# dev_kit.net
KiCad netlist of a schematic drawn in EasyEDA
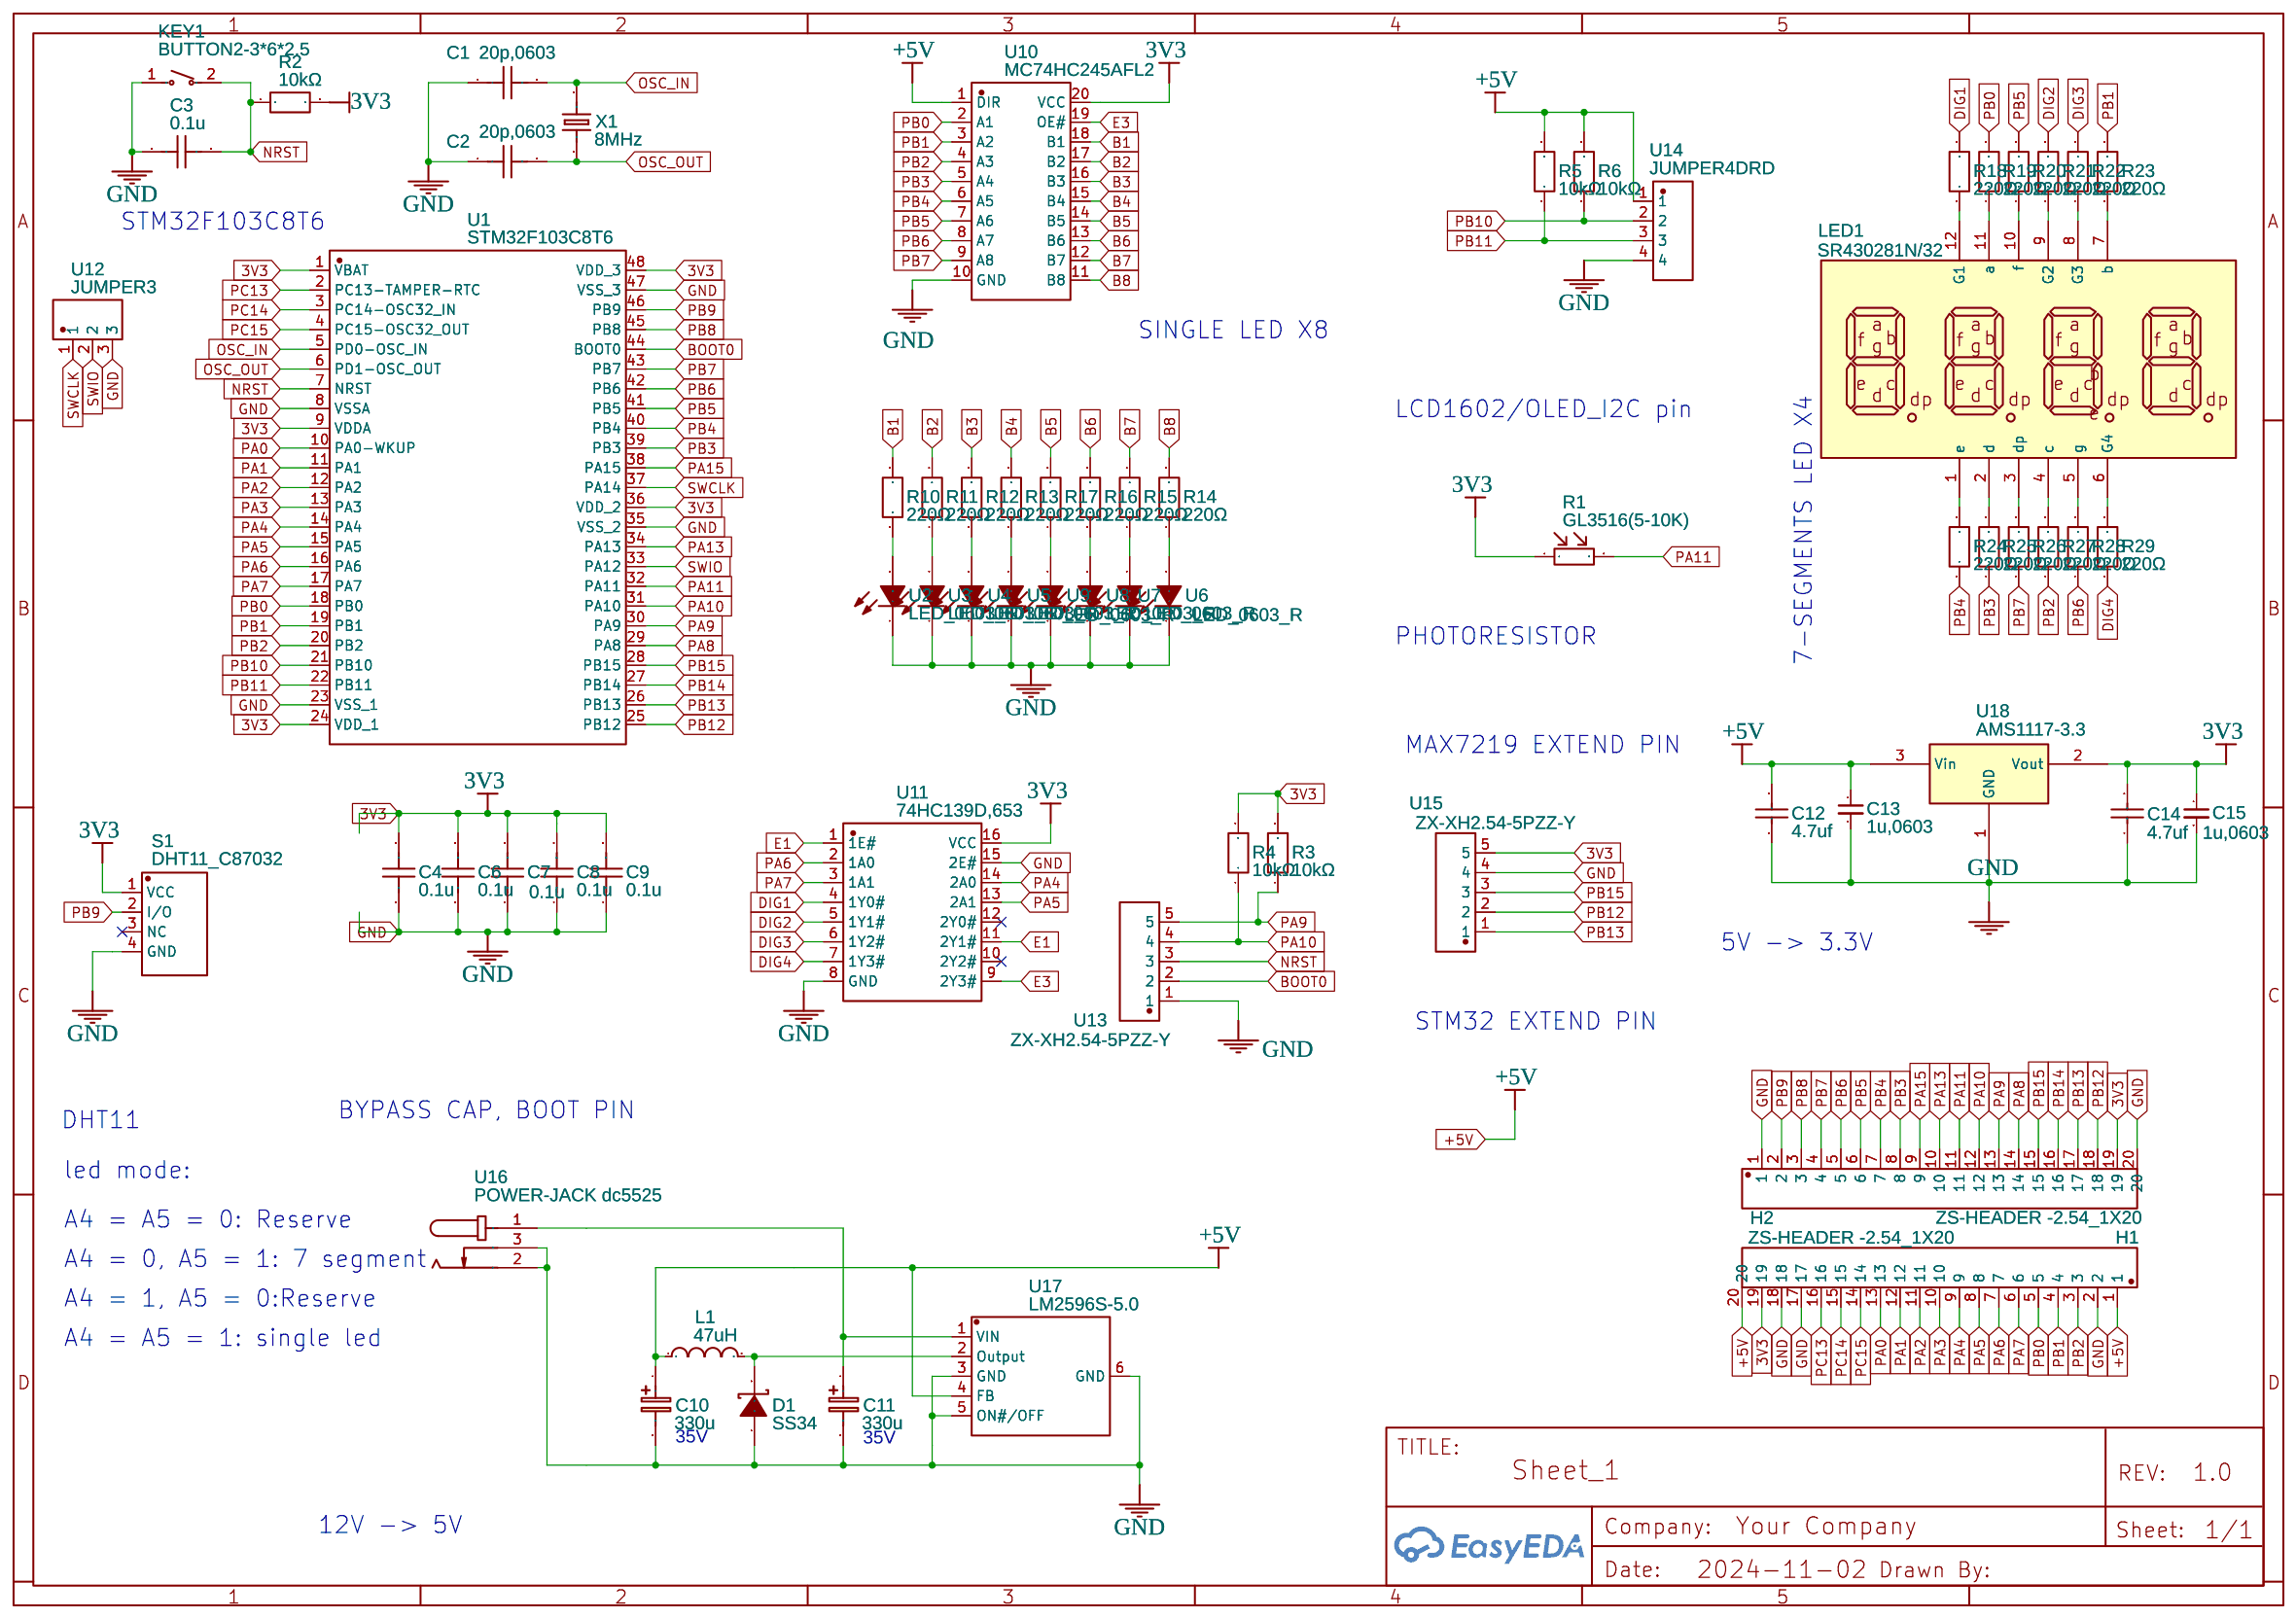
[diagram p0: schematic sheet]

(export (version "E")
  (design (tool "Eeschema 10.0.6"))
  (components
    (comp (ref "C1") (value "20p,0603") (libsource (lib "") (part "C_0603_US_1")))
    (comp (ref "C2") (value "20p,0603") (libsource (lib "") (part "C_0603_US_1")))
    (comp (ref "C3") (value "0.1u") (libsource (lib "") (part "C_0603_US_1")))
    (comp (ref "C4") (value "0.1u") (libsource (lib "") (part "C_0603_US")))
    (comp (ref "C6") (value "0.1u") (libsource (lib "") (part "C_0603_US")))
    (comp (ref "C7") (value "0.1u") (libsource (lib "") (part "C_0603_US")))
    (comp (ref "C8") (value "0.1u") (libsource (lib "") (part "C_0603_US")))
    (comp (ref "C9") (value "0.1u") (libsource (lib "") (part "C_0603_US")))
    (comp (ref "C10")
      (value "330u")
      (fields (field (name "Manufacturer Part") "?"))
      (libsource (lib "") (part "Cap_Electrolytic(SMD)_D8.0XH10.5_EU"))
    )
    (comp (ref "C11")
      (value "330u")
      (fields (field (name "Manufacturer Part") "?"))
      (libsource (lib "") (part "Cap_Electrolytic(SMD)_D8.0XH10.5_EU"))
    )
    (comp (ref "C12")
      (value "4.7uf")
      (fields (field (name "Manufacturer Part") "?"))
      (libsource (lib "") (part "Unknown_890_-400"))
    )
    (comp (ref "C13") (value "1u,0603") (libsource (lib "") (part "C_0603")))
    (comp (ref "C14")
      (value "4.7uf")
      (fields (field (name "Manufacturer Part") "?"))
      (libsource (lib "") (part "Unknown_1070_-400"))
    )
    (comp (ref "C15") (value "1u,0603") (libsource (lib "") (part "C_0603")))
    (comp (ref "D1")
      (value "SS34")
      (fields (field (name "Manufacturer") "Yenji"))
      (libsource (lib "") (part "Unknown_375_-105"))
    )
    (comp (ref "H1") (value "ZS-HEADER -2.54_1X20") (libsource (lib "") (part "ZS-HEADER -2.54_1X20")))
    (comp (ref "H2") (value "ZS-HEADER -2.54_1X20") (libsource (lib "") (part "ZS-HEADER -2.54_1X20_1")))
    (comp (ref "KEY1") (value "BUTTON2-3*6*2.5") (libsource (lib "") (part "BUTTON2-3*6*2.5")))
    (comp (ref "L1")
      (value "47uH")
      (fields (field (name "Manufacturer Part") "CDRH127NP-470MC") (field (name "Manufacturer") "Sumida"))
      (libsource (lib "") (part "CDRH127NP-470MC"))
    )
    (comp (ref "LED1")
      (value "SR430281N/32")
      (fields (field (name "Manufacturer") "ARKLED(方舟)"))
      (libsource (lib "") (part "SR430281N/32"))
    )
    (comp (ref "R1")
      (value "GL3516(5-10K)")
      (fields (field (name "Manufacturer Part") "GL3516（5-10K）") (field (name "Manufacturer") "JCHL(晶创和立)"))
      (libsource (lib "") (part "GL3516(5-10K)"))
    )
    (comp (ref "R2")
      (value "10kΩ")
      (fields (field (name "Manufacturer Part") "TD03E1002BT") (field (name "Manufacturer") "FH(风华)"))
      (libsource (lib "") (part "TD03E1002BT_1"))
    )
    (comp (ref "R3")
      (value "10kΩ")
      (fields (field (name "Manufacturer Part") "TD03E1002BT") (field (name "Manufacturer") "FH(风华)"))
      (libsource (lib "") (part "TD03E1002BT"))
    )
    (comp (ref "R4")
      (value "10kΩ")
      (fields (field (name "Manufacturer Part") "TD03E1002BT") (field (name "Manufacturer") "FH(风华)"))
      (libsource (lib "") (part "TD03E1002BT"))
    )
    (comp (ref "R5")
      (value "10kΩ")
      (fields (field (name "Manufacturer Part") "TD03E1002BT") (field (name "Manufacturer") "FH(风华)"))
      (libsource (lib "") (part "TD03E1002BT"))
    )
    (comp (ref "R6")
      (value "10kΩ")
      (fields (field (name "Manufacturer Part") "TD03E1002BT") (field (name "Manufacturer") "FH(风华)"))
      (libsource (lib "") (part "TD03E1002BT"))
    )
    (comp (ref "R10")
      (value "220Ω")
      (fields
        (field (name "Manufacturer Part") "CRCW0603220RFKEA")
        (field (name "Manufacturer") "VISHAY(威世)")
      )
      (libsource (lib "") (part "CRCW0603220RFKEA"))
    )
    (comp (ref "R11")
      (value "220Ω")
      (fields
        (field (name "Manufacturer Part") "CRCW0603220RFKEA")
        (field (name "Manufacturer") "VISHAY(威世)")
      )
      (libsource (lib "") (part "CRCW0603220RFKEA"))
    )
    (comp (ref "R12")
      (value "220Ω")
      (fields
        (field (name "Manufacturer Part") "CRCW0603220RFKEA")
        (field (name "Manufacturer") "VISHAY(威世)")
      )
      (libsource (lib "") (part "CRCW0603220RFKEA"))
    )
    (comp (ref "R13")
      (value "220Ω")
      (fields
        (field (name "Manufacturer Part") "CRCW0603220RFKEA")
        (field (name "Manufacturer") "VISHAY(威世)")
      )
      (libsource (lib "") (part "CRCW0603220RFKEA"))
    )
    (comp (ref "R14")
      (value "220Ω")
      (fields
        (field (name "Manufacturer Part") "CRCW0603220RFKEA")
        (field (name "Manufacturer") "VISHAY(威世)")
      )
      (libsource (lib "") (part "CRCW0603220RFKEA"))
    )
    (comp (ref "R15")
      (value "220Ω")
      (fields
        (field (name "Manufacturer Part") "CRCW0603220RFKEA")
        (field (name "Manufacturer") "VISHAY(威世)")
      )
      (libsource (lib "") (part "CRCW0603220RFKEA"))
    )
    (comp (ref "R16")
      (value "220Ω")
      (fields
        (field (name "Manufacturer Part") "CRCW0603220RFKEA")
        (field (name "Manufacturer") "VISHAY(威世)")
      )
      (libsource (lib "") (part "CRCW0603220RFKEA"))
    )
    (comp (ref "R17")
      (value "220Ω")
      (fields
        (field (name "Manufacturer Part") "CRCW0603220RFKEA")
        (field (name "Manufacturer") "VISHAY(威世)")
      )
      (libsource (lib "") (part "CRCW0603220RFKEA"))
    )
    (comp (ref "R18")
      (value "220Ω")
      (fields
        (field (name "Manufacturer Part") "CRCW0603220RFKEA")
        (field (name "Manufacturer") "VISHAY(威世)")
      )
      (libsource (lib "") (part "CRCW0603220RFKEA"))
    )
    (comp (ref "R19")
      (value "220Ω")
      (fields
        (field (name "Manufacturer Part") "CRCW0603220RFKEA")
        (field (name "Manufacturer") "VISHAY(威世)")
      )
      (libsource (lib "") (part "CRCW0603220RFKEA"))
    )
    (comp (ref "R20")
      (value "220Ω")
      (fields
        (field (name "Manufacturer Part") "CRCW0603220RFKEA")
        (field (name "Manufacturer") "VISHAY(威世)")
      )
      (libsource (lib "") (part "CRCW0603220RFKEA"))
    )
    (comp (ref "R21")
      (value "220Ω")
      (fields
        (field (name "Manufacturer Part") "CRCW0603220RFKEA")
        (field (name "Manufacturer") "VISHAY(威世)")
      )
      (libsource (lib "") (part "CRCW0603220RFKEA"))
    )
    (comp (ref "R22")
      (value "220Ω")
      (fields
        (field (name "Manufacturer Part") "CRCW0603220RFKEA")
        (field (name "Manufacturer") "VISHAY(威世)")
      )
      (libsource (lib "") (part "CRCW0603220RFKEA"))
    )
    (comp (ref "R23")
      (value "220Ω")
      (fields
        (field (name "Manufacturer Part") "CRCW0603220RFKEA")
        (field (name "Manufacturer") "VISHAY(威世)")
      )
      (libsource (lib "") (part "CRCW0603220RFKEA"))
    )
    (comp (ref "R24")
      (value "220Ω")
      (fields
        (field (name "Manufacturer Part") "CRCW0603220RFKEA")
        (field (name "Manufacturer") "VISHAY(威世)")
      )
      (libsource (lib "") (part "CRCW0603220RFKEA"))
    )
    (comp (ref "R25")
      (value "220Ω")
      (fields
        (field (name "Manufacturer Part") "CRCW0603220RFKEA")
        (field (name "Manufacturer") "VISHAY(威世)")
      )
      (libsource (lib "") (part "CRCW0603220RFKEA"))
    )
    (comp (ref "R26")
      (value "220Ω")
      (fields
        (field (name "Manufacturer Part") "CRCW0603220RFKEA")
        (field (name "Manufacturer") "VISHAY(威世)")
      )
      (libsource (lib "") (part "CRCW0603220RFKEA"))
    )
    (comp (ref "R27")
      (value "220Ω")
      (fields
        (field (name "Manufacturer Part") "CRCW0603220RFKEA")
        (field (name "Manufacturer") "VISHAY(威世)")
      )
      (libsource (lib "") (part "CRCW0603220RFKEA"))
    )
    (comp (ref "R28")
      (value "220Ω")
      (fields
        (field (name "Manufacturer Part") "CRCW0603220RFKEA")
        (field (name "Manufacturer") "VISHAY(威世)")
      )
      (libsource (lib "") (part "CRCW0603220RFKEA"))
    )
    (comp (ref "R29")
      (value "220Ω")
      (fields
        (field (name "Manufacturer Part") "CRCW0603220RFKEA")
        (field (name "Manufacturer") "VISHAY(威世)")
      )
      (libsource (lib "") (part "CRCW0603220RFKEA"))
    )
    (comp (ref "S1")
      (value "DHT11_C87032")
      (fields (field (name "Manufacturer Part") "DHT11") (field (name "Manufacturer") "AOSONG"))
      (libsource (lib "") (part "DHT11_C87032"))
    )
    (comp (ref "U1")
      (value "STM32F103C8T6")
      (fields (field (name "Manufacturer") "ST(意法半导体)"))
      (libsource (lib "") (part "STM32F103C8T6"))
    )
    (comp (ref "U2") (value "LED_0603_R") (libsource (lib "") (part "LED_0603_R")))
    (comp (ref "U3") (value "LED_0603_R") (libsource (lib "") (part "LED_0603_R")))
    (comp (ref "U4") (value "LED_0603_R") (libsource (lib "") (part "LED_0603_R")))
    (comp (ref "U5") (value "LED_0603_R") (libsource (lib "") (part "LED_0603_R")))
    (comp (ref "U6") (value "LED_0603_R") (libsource (lib "") (part "LED_0603_R")))
    (comp (ref "U7") (value "LED_0603_R") (libsource (lib "") (part "LED_0603_R")))
    (comp (ref "U8") (value "LED_0603_R") (libsource (lib "") (part "LED_0603_R")))
    (comp (ref "U9") (value "LED_0603_R") (libsource (lib "") (part "LED_0603_R")))
    (comp (ref "U10")
      (value "MC74HC245AFL2")
      (fields (field (name "Manufacturer") "MOTOROLA(摩托罗拉)"))
      (libsource (lib "") (part "MC74HC245AFL2"))
    )
    (comp (ref "U11")
      (value "74HC139D,653")
      (fields (field (name "Manufacturer") "Nexperia(安世)"))
      (libsource (lib "") (part "74HC139D,653"))
    )
    (comp (ref "U12")
      (value "JUMPER3")
      (fields (field (name "Manufacturer Part") "Jumper3"))
      (libsource (lib "") (part "JUMPER3"))
    )
    (comp (ref "U13")
      (value "ZX-XH2.54-5PZZ-Y")
      (fields (field (name "Manufacturer") "Megastar(兆星)"))
      (libsource (lib "") (part "ZX-XH2.54-5PZZ-Y"))
    )
    (comp (ref "U14")
      (value "JUMPER4DRD")
      (fields (field (name "Manufacturer Part") "Jumper4"))
      (libsource (lib "") (part "JUMPER4DRD"))
    )
    (comp (ref "U15")
      (value "ZX-XH2.54-5PZZ-Y")
      (fields (field (name "Manufacturer") "Megastar(兆星)"))
      (libsource (lib "") (part "ZX-XH2.54-5PZZ-Y"))
    )
    (comp (ref "U16")
      (value "POWER-JACK dc5525")
      (fields (field (name "Manufacturer Part") "POWER-JACK"))
      (libsource (lib "") (part "POWER-JACK dc5525"))
    )
    (comp (ref "U17")
      (value "LM2596S-5.0")
      (fields
        (field (name "Manufacturer Part") "LM2596S-5.0/NOPB")
        (field (name "Manufacturer") "Texas Instruments")
      )
      (libsource (lib "") (part "Unknown_520_-120"))
    )
    (comp (ref "U18")
      (value "AMS1117-3.3")
      (fields (field (name "Manufacturer Part") "?"))
      (libsource (lib "") (part "Unknown_1000_-420"))
    )
    (comp (ref "X1")
      (value "8MHz")
      (fields
        (field (name "Manufacturer Part") "49S-8.00-20-10-10/A")
        (field (name "Manufacturer") "LIMING(利明)")
      )
      (libsource (lib "") (part "49S-8.00-20-10-10/A"))
    )
  )
  (nets
    (net (code "1") (name "+5V") (class "Default")
      (node (ref "C10") (pin "1") (pinfunction "1_1") (pintype "unspecified"))
      (node (ref "C12") (pin "2") (pinfunction "2_2") (pintype "unspecified"))
      (node (ref "C13") (pin "1") (pintype "unspecified"))
      (node (ref "H2") (pin "1") (pinfunction "1_1") (pintype "unspecified"))
      (node (ref "H2") (pin "20") (pinfunction "20_20") (pintype "unspecified"))
      (node (ref "L1") (pin "1") (pinfunction "1_1") (pintype "unspecified"))
      (node (ref "R5") (pin "2") (pinfunction "2_2") (pintype "unspecified"))
      (node (ref "R6") (pin "2") (pinfunction "2_2") (pintype "unspecified"))
      (node (ref "U10") (pin "1") (pinfunction "DIR_1") (pintype "unspecified"))
      (node (ref "U14") (pin "1") (pinfunction "1_1") (pintype "unspecified"))
      (node (ref "U17") (pin "4") (pinfunction "FB_4") (pintype "unspecified"))
      (node (ref "U18") (pin "3") (pinfunction "Vin_3") (pintype "unspecified"))
    )
    (net (code "2") (name "3V3") (class "Default")
      (node (ref "C14") (pin "2") (pinfunction "2_2") (pintype "unspecified"))
      (node (ref "C15") (pin "1") (pintype "unspecified"))
      (node (ref "C4") (pin "2") (pinfunction "2_2") (pintype "unspecified"))
      (node (ref "C6") (pin "2") (pinfunction "2_2") (pintype "unspecified"))
      (node (ref "C7") (pin "2") (pinfunction "2_2") (pintype "unspecified"))
      (node (ref "C8") (pin "2") (pinfunction "2_2") (pintype "unspecified"))
      (node (ref "C9") (pin "2") (pinfunction "2_2") (pintype "unspecified"))
      (node (ref "H1") (pin "19") (pinfunction "19_19") (pintype "unspecified"))
      (node (ref "H2") (pin "19") (pinfunction "19_19") (pintype "unspecified"))
      (node (ref "R1") (pin "1") (pinfunction "1_1") (pintype "input"))
      (node (ref "R2") (pin "2") (pinfunction "2_2") (pintype "unspecified"))
      (node (ref "R3") (pin "2") (pinfunction "2_2") (pintype "unspecified"))
      (node (ref "R4") (pin "2") (pinfunction "2_2") (pintype "unspecified"))
      (node (ref "S1") (pin "1") (pinfunction "VCC_1") (pintype "unspecified"))
      (node (ref "U1") (pin "1") (pinfunction "VBAT_1") (pintype "unspecified"))
      (node (ref "U1") (pin "24") (pinfunction "VDD_1_24") (pintype "unspecified"))
      (node (ref "U1") (pin "36") (pinfunction "VDD_2_36") (pintype "unspecified"))
      (node (ref "U1") (pin "48") (pinfunction "VDD_3_48") (pintype "unspecified"))
      (node (ref "U1") (pin "9") (pinfunction "VDDA_9") (pintype "unspecified"))
      (node (ref "U10") (pin "20") (pinfunction "VCC_20") (pintype "unspecified"))
      (node (ref "U11") (pin "16") (pinfunction "VCC_16") (pintype "unspecified"))
      (node (ref "U15") (pin "5") (pinfunction "5_5") (pintype "unspecified"))
      (node (ref "U18") (pin "2") (pinfunction "Vout_2") (pintype "unspecified"))
    )
    (net (code "3") (name "B1") (class "Default")
      (node (ref "R10") (pin "2") (pinfunction "2_2") (pintype "unspecified"))
      (node (ref "U10") (pin "18") (pinfunction "B1_18") (pintype "unspecified"))
    )
    (net (code "4") (name "B2") (class "Default")
      (node (ref "R11") (pin "2") (pinfunction "2_2") (pintype "unspecified"))
      (node (ref "U10") (pin "17") (pinfunction "B2_17") (pintype "unspecified"))
    )
    (net (code "5") (name "B3") (class "Default")
      (node (ref "R12") (pin "2") (pinfunction "2_2") (pintype "unspecified"))
      (node (ref "U10") (pin "16") (pinfunction "B3_16") (pintype "unspecified"))
    )
    (net (code "6") (name "B4") (class "Default")
      (node (ref "R13") (pin "2") (pinfunction "2_2") (pintype "unspecified"))
      (node (ref "U10") (pin "15") (pinfunction "B4_15") (pintype "unspecified"))
    )
    (net (code "7") (name "B5") (class "Default")
      (node (ref "R17") (pin "2") (pinfunction "2_2") (pintype "unspecified"))
      (node (ref "U10") (pin "14") (pinfunction "B5_14") (pintype "unspecified"))
    )
    (net (code "8") (name "B6") (class "Default")
      (node (ref "R16") (pin "2") (pinfunction "2_2") (pintype "unspecified"))
      (node (ref "U10") (pin "13") (pinfunction "B6_13") (pintype "unspecified"))
    )
    (net (code "9") (name "B7") (class "Default")
      (node (ref "R15") (pin "2") (pinfunction "2_2") (pintype "unspecified"))
      (node (ref "U10") (pin "12") (pinfunction "B7_12") (pintype "unspecified"))
    )
    (net (code "10") (name "B8") (class "Default")
      (node (ref "R14") (pin "2") (pinfunction "2_2") (pintype "unspecified"))
      (node (ref "U10") (pin "11") (pinfunction "B8_11") (pintype "unspecified"))
    )
    (net (code "11") (name "BOOT0") (class "Default")
      (node (ref "U1") (pin "44") (pinfunction "BOOT0_44") (pintype "unspecified"))
      (node (ref "U13") (pin "2") (pinfunction "2_2") (pintype "unspecified"))
    )
    (net (code "12") (name "DIG1") (class "Default")
      (node (ref "R18") (pin "2") (pinfunction "2_2") (pintype "unspecified"))
      (node (ref "U11") (pin "4") (pinfunction "1Y0#_4") (pintype "unspecified"))
    )
    (net (code "13") (name "DIG2") (class "Default")
      (node (ref "R21") (pin "2") (pinfunction "2_2") (pintype "unspecified"))
      (node (ref "U11") (pin "5") (pinfunction "1Y1#_5") (pintype "unspecified"))
    )
    (net (code "14") (name "DIG3") (class "Default")
      (node (ref "R22") (pin "2") (pinfunction "2_2") (pintype "unspecified"))
      (node (ref "U11") (pin "6") (pinfunction "1Y2#_6") (pintype "unspecified"))
    )
    (net (code "15") (name "DIG4") (class "Default")
      (node (ref "R29") (pin "1") (pinfunction "1_1") (pintype "unspecified"))
      (node (ref "U11") (pin "7") (pinfunction "1Y3#_7") (pintype "unspecified"))
    )
    (net (code "16") (name "E1") (class "Default")
      (node (ref "U11") (pin "1") (pinfunction "1E#_1") (pintype "unspecified"))
      (node (ref "U11") (pin "11") (pinfunction "2Y1#_11") (pintype "unspecified"))
    )
    (net (code "17") (name "E3") (class "Default")
      (node (ref "U10") (pin "19") (pinfunction "OE#_19") (pintype "unspecified"))
      (node (ref "U11") (pin "9") (pinfunction "2Y3#_9") (pintype "unspecified"))
    )
    (net (code "18") (name "GND") (class "Default")
      (node (ref "C1") (pin "1") (pinfunction "1_1") (pintype "unspecified"))
      (node (ref "C10") (pin "2") (pinfunction "2_2") (pintype "unspecified"))
      (node (ref "C11") (pin "2") (pinfunction "2_2") (pintype "unspecified"))
      (node (ref "C12") (pin "1") (pinfunction "1_1") (pintype "unspecified"))
      (node (ref "C13") (pin "2") (pintype "unspecified"))
      (node (ref "C14") (pin "1") (pinfunction "1_1") (pintype "unspecified"))
      (node (ref "C15") (pin "2") (pintype "unspecified"))
      (node (ref "C2") (pin "1") (pinfunction "1_1") (pintype "unspecified"))
      (node (ref "C3") (pin "1") (pinfunction "1_1") (pintype "unspecified"))
      (node (ref "C4") (pin "1") (pinfunction "1_1") (pintype "unspecified"))
      (node (ref "C6") (pin "1") (pinfunction "1_1") (pintype "unspecified"))
      (node (ref "C7") (pin "1") (pinfunction "1_1") (pintype "unspecified"))
      (node (ref "C8") (pin "1") (pinfunction "1_1") (pintype "unspecified"))
      (node (ref "C9") (pin "1") (pinfunction "1_1") (pintype "unspecified"))
      (node (ref "D1") (pin "1") (pinfunction "A_1") (pintype "unspecified"))
      (node (ref "H1") (pin "1") (pinfunction "1_1") (pintype "unspecified"))
      (node (ref "H1") (pin "20") (pinfunction "20_20") (pintype "unspecified"))
      (node (ref "H2") (pin "17") (pinfunction "17_17") (pintype "unspecified"))
      (node (ref "H2") (pin "18") (pinfunction "18_18") (pintype "unspecified"))
      (node (ref "H2") (pin "2") (pinfunction "2_2") (pintype "unspecified"))
      (node (ref "KEY1") (pin "1") (pinfunction "1_1") (pintype "unspecified"))
      (node (ref "S1") (pin "4") (pinfunction "GND_4") (pintype "unspecified"))
      (node (ref "U1") (pin "23") (pinfunction "VSS_1_23") (pintype "unspecified"))
      (node (ref "U1") (pin "35") (pinfunction "VSS_2_35") (pintype "unspecified"))
      (node (ref "U1") (pin "47") (pinfunction "VSS_3_47") (pintype "unspecified"))
      (node (ref "U1") (pin "8") (pinfunction "VSSA_8") (pintype "unspecified"))
      (node (ref "U10") (pin "10") (pinfunction "GND_10") (pintype "unspecified"))
      (node (ref "U11") (pin "15") (pinfunction "2E#_15") (pintype "unspecified"))
      (node (ref "U11") (pin "8") (pinfunction "GND_8") (pintype "unspecified"))
      (node (ref "U12") (pin "3") (pinfunction "3_3") (pintype "unspecified"))
      (node (ref "U13") (pin "1") (pinfunction "1_1") (pintype "unspecified"))
      (node (ref "U14") (pin "4") (pinfunction "4_4") (pintype "unspecified"))
      (node (ref "U15") (pin "4") (pinfunction "4_4") (pintype "unspecified"))
      (node (ref "U16") (pin "2") (pinfunction "2_2") (pintype "unspecified"))
      (node (ref "U16") (pin "3") (pinfunction "3_3") (pintype "unspecified"))
      (node (ref "U17") (pin "3") (pinfunction "GND_3") (pintype "unspecified"))
      (node (ref "U17") (pin "5") (pinfunction "ON#/OFF_5") (pintype "unspecified"))
      (node (ref "U17") (pin "6") (pinfunction "GND_6") (pintype "unspecified"))
      (node (ref "U18") (pin "1") (pinfunction "GND_1") (pintype "unspecified"))
      (node (ref "U2") (pin "1") (pinfunction "-_1") (pintype "input"))
      (node (ref "U3") (pin "1") (pinfunction "-_1") (pintype "input"))
      (node (ref "U4") (pin "1") (pinfunction "-_1") (pintype "input"))
      (node (ref "U5") (pin "1") (pinfunction "-_1") (pintype "input"))
      (node (ref "U6") (pin "1") (pinfunction "-_1") (pintype "input"))
      (node (ref "U7") (pin "1") (pinfunction "-_1") (pintype "input"))
      (node (ref "U8") (pin "1") (pinfunction "-_1") (pintype "input"))
      (node (ref "U9") (pin "1") (pinfunction "-_1") (pintype "input"))
    )
    (net (code "19") (name "NRST") (class "Default")
      (node (ref "C3") (pin "2") (pinfunction "2_2") (pintype "unspecified"))
      (node (ref "KEY1") (pin "2") (pinfunction "2_2") (pintype "unspecified"))
      (node (ref "R2") (pin "1") (pinfunction "1_1") (pintype "unspecified"))
      (node (ref "U1") (pin "7") (pinfunction "NRST_7") (pintype "unspecified"))
      (node (ref "U13") (pin "3") (pinfunction "3_3") (pintype "unspecified"))
    )
    (net (code "20") (name "Net-(D1-K)") (class "Default")
      (node (ref "D1") (pin "2") (pinfunction "K_2") (pintype "unspecified"))
      (node (ref "L1") (pin "2") (pinfunction "2_2") (pintype "unspecified"))
      (node (ref "U17") (pin "2") (pinfunction "Output_2") (pintype "unspecified"))
    )
    (net (code "21") (name "Net-(LED1-G1)") (class "Default")
      (node (ref "LED1") (pin "12") (pinfunction "G1_12") (pintype "input"))
      (node (ref "R18") (pin "1") (pinfunction "1_1") (pintype "unspecified"))
    )
    (net (code "22") (name "Net-(LED1-G2)") (class "Default")
      (node (ref "LED1") (pin "9") (pinfunction "G2_9") (pintype "input"))
      (node (ref "R21") (pin "1") (pinfunction "1_1") (pintype "unspecified"))
    )
    (net (code "23") (name "Net-(LED1-G3)") (class "Default")
      (node (ref "LED1") (pin "8") (pinfunction "G3_8") (pintype "input"))
      (node (ref "R22") (pin "1") (pinfunction "1_1") (pintype "unspecified"))
    )
    (net (code "24") (name "Net-(LED1-G4)") (class "Default")
      (node (ref "LED1") (pin "6") (pinfunction "G4_6") (pintype "input"))
      (node (ref "R29") (pin "2") (pinfunction "2_2") (pintype "unspecified"))
    )
    (net (code "25") (name "Net-(LED1-a)") (class "Default")
      (node (ref "LED1") (pin "11") (pinfunction "a_11") (pintype "input"))
      (node (ref "R19") (pin "1") (pinfunction "1_1") (pintype "unspecified"))
    )
    (net (code "26") (name "Net-(LED1-b)") (class "Default")
      (node (ref "LED1") (pin "7") (pinfunction "b_7") (pintype "input"))
      (node (ref "R23") (pin "1") (pinfunction "1_1") (pintype "unspecified"))
    )
    (net (code "27") (name "Net-(LED1-c)") (class "Default")
      (node (ref "LED1") (pin "4") (pinfunction "c_4") (pintype "input"))
      (node (ref "R27") (pin "2") (pinfunction "2_2") (pintype "unspecified"))
    )
    (net (code "28") (name "Net-(LED1-d)") (class "Default")
      (node (ref "LED1") (pin "2") (pinfunction "d_2") (pintype "input"))
      (node (ref "R25") (pin "2") (pinfunction "2_2") (pintype "unspecified"))
    )
    (net (code "29") (name "Net-(LED1-dp)") (class "Default")
      (node (ref "LED1") (pin "3") (pinfunction "dp_3") (pintype "input"))
      (node (ref "R26") (pin "2") (pinfunction "2_2") (pintype "unspecified"))
    )
    (net (code "30") (name "Net-(LED1-e)") (class "Default")
      (node (ref "LED1") (pin "1") (pinfunction "e_1") (pintype "input"))
      (node (ref "R24") (pin "2") (pinfunction "2_2") (pintype "unspecified"))
    )
    (net (code "31") (name "Net-(LED1-f)") (class "Default")
      (node (ref "LED1") (pin "10") (pinfunction "f_10") (pintype "input"))
      (node (ref "R20") (pin "1") (pinfunction "1_1") (pintype "unspecified"))
    )
    (net (code "32") (name "Net-(LED1-g)") (class "Default")
      (node (ref "LED1") (pin "5") (pinfunction "g_5") (pintype "input"))
      (node (ref "R28") (pin "2") (pinfunction "2_2") (pintype "unspecified"))
    )
    (net (code "33") (name "Net-(U2-+)") (class "Default")
      (node (ref "R10") (pin "1") (pinfunction "1_1") (pintype "unspecified"))
      (node (ref "U2") (pin "2") (pinfunction "+_2") (pintype "input"))
    )
    (net (code "34") (name "Net-(U3-+)") (class "Default")
      (node (ref "R11") (pin "1") (pinfunction "1_1") (pintype "unspecified"))
      (node (ref "U3") (pin "2") (pinfunction "+_2") (pintype "input"))
    )
    (net (code "35") (name "Net-(U4-+)") (class "Default")
      (node (ref "R12") (pin "1") (pinfunction "1_1") (pintype "unspecified"))
      (node (ref "U4") (pin "2") (pinfunction "+_2") (pintype "input"))
    )
    (net (code "36") (name "Net-(U5-+)") (class "Default")
      (node (ref "R13") (pin "1") (pinfunction "1_1") (pintype "unspecified"))
      (node (ref "U5") (pin "2") (pinfunction "+_2") (pintype "input"))
    )
    (net (code "37") (name "Net-(U6-+)") (class "Default")
      (node (ref "R14") (pin "1") (pinfunction "1_1") (pintype "unspecified"))
      (node (ref "U6") (pin "2") (pinfunction "+_2") (pintype "input"))
    )
    (net (code "38") (name "Net-(U7-+)") (class "Default")
      (node (ref "R15") (pin "1") (pinfunction "1_1") (pintype "unspecified"))
      (node (ref "U7") (pin "2") (pinfunction "+_2") (pintype "input"))
    )
    (net (code "39") (name "Net-(U8-+)") (class "Default")
      (node (ref "R16") (pin "1") (pinfunction "1_1") (pintype "unspecified"))
      (node (ref "U8") (pin "2") (pinfunction "+_2") (pintype "input"))
    )
    (net (code "40") (name "Net-(U9-+)") (class "Default")
      (node (ref "R17") (pin "1") (pinfunction "1_1") (pintype "unspecified"))
      (node (ref "U9") (pin "2") (pinfunction "+_2") (pintype "input"))
    )
    (net (code "41") (name "Net-(U17-VIN)") (class "Default")
      (node (ref "C11") (pin "1") (pinfunction "1_1") (pintype "unspecified"))
      (node (ref "U16") (pin "1") (pinfunction "1_1") (pintype "unspecified"))
      (node (ref "U17") (pin "1") (pinfunction "VIN_1") (pintype "unspecified"))
    )
    (net (code "42") (name "OSC_IN") (class "Default")
      (node (ref "C1") (pin "2") (pinfunction "2_2") (pintype "unspecified"))
      (node (ref "U1") (pin "5") (pinfunction "PD0-OSC_IN_5") (pintype "unspecified"))
      (node (ref "X1") (pin "2") (pinfunction "2_2") (pintype "unspecified"))
    )
    (net (code "43") (name "OSC_OUT") (class "Default")
      (node (ref "C2") (pin "2") (pinfunction "2_2") (pintype "unspecified"))
      (node (ref "U1") (pin "6") (pinfunction "PD1-OSC_OUT_6") (pintype "unspecified"))
      (node (ref "X1") (pin "1") (pinfunction "1_1") (pintype "unspecified"))
    )
    (net (code "44") (name "PA0") (class "Default")
      (node (ref "H2") (pin "13") (pinfunction "13_13") (pintype "unspecified"))
      (node (ref "U1") (pin "10") (pinfunction "PA0-WKUP_10") (pintype "unspecified"))
    )
    (net (code "45") (name "PA1") (class "Default")
      (node (ref "H2") (pin "12") (pinfunction "12_12") (pintype "unspecified"))
      (node (ref "U1") (pin "11") (pinfunction "PA1_11") (pintype "unspecified"))
    )
    (net (code "46") (name "PA2") (class "Default")
      (node (ref "H2") (pin "11") (pinfunction "11_11") (pintype "unspecified"))
      (node (ref "U1") (pin "12") (pinfunction "PA2_12") (pintype "unspecified"))
    )
    (net (code "47") (name "PA3") (class "Default")
      (node (ref "H2") (pin "10") (pinfunction "10_10") (pintype "unspecified"))
      (node (ref "U1") (pin "13") (pinfunction "PA3_13") (pintype "unspecified"))
    )
    (net (code "48") (name "PA4") (class "Default")
      (node (ref "H2") (pin "9") (pinfunction "9_9") (pintype "unspecified"))
      (node (ref "U1") (pin "14") (pinfunction "PA4_14") (pintype "unspecified"))
      (node (ref "U11") (pin "14") (pinfunction "2A0_14") (pintype "unspecified"))
    )
    (net (code "49") (name "PA5") (class "Default")
      (node (ref "H2") (pin "8") (pinfunction "8_8") (pintype "unspecified"))
      (node (ref "U1") (pin "15") (pinfunction "PA5_15") (pintype "unspecified"))
      (node (ref "U11") (pin "13") (pinfunction "2A1_13") (pintype "unspecified"))
    )
    (net (code "50") (name "PA6") (class "Default")
      (node (ref "H2") (pin "7") (pinfunction "7_7") (pintype "unspecified"))
      (node (ref "U1") (pin "16") (pinfunction "PA6_16") (pintype "unspecified"))
      (node (ref "U11") (pin "2") (pinfunction "1A0_2") (pintype "unspecified"))
    )
    (net (code "51") (name "PA7") (class "Default")
      (node (ref "H2") (pin "6") (pinfunction "6_6") (pintype "unspecified"))
      (node (ref "U1") (pin "17") (pinfunction "PA7_17") (pintype "unspecified"))
      (node (ref "U11") (pin "3") (pinfunction "1A1_3") (pintype "unspecified"))
    )
    (net (code "52") (name "PA8") (class "Default")
      (node (ref "H1") (pin "14") (pinfunction "14_14") (pintype "unspecified"))
      (node (ref "U1") (pin "29") (pinfunction "PA8_29") (pintype "unspecified"))
    )
    (net (code "53") (name "PA9") (class "Default")
      (node (ref "H1") (pin "13") (pinfunction "13_13") (pintype "unspecified"))
      (node (ref "R3") (pin "1") (pinfunction "1_1") (pintype "unspecified"))
      (node (ref "U1") (pin "30") (pinfunction "PA9_30") (pintype "unspecified"))
      (node (ref "U13") (pin "5") (pinfunction "5_5") (pintype "unspecified"))
    )
    (net (code "54") (name "PA10") (class "Default")
      (node (ref "H1") (pin "12") (pinfunction "12_12") (pintype "unspecified"))
      (node (ref "R4") (pin "1") (pinfunction "1_1") (pintype "unspecified"))
      (node (ref "U1") (pin "31") (pinfunction "PA10_31") (pintype "unspecified"))
      (node (ref "U13") (pin "4") (pinfunction "4_4") (pintype "unspecified"))
    )
    (net (code "55") (name "PA11") (class "Default")
      (node (ref "H1") (pin "11") (pinfunction "11_11") (pintype "unspecified"))
      (node (ref "R1") (pin "2") (pinfunction "2_2") (pintype "input"))
      (node (ref "U1") (pin "32") (pinfunction "PA11_32") (pintype "unspecified"))
    )
    (net (code "56") (name "PA13") (class "Default")
      (node (ref "H1") (pin "10") (pinfunction "10_10") (pintype "unspecified"))
      (node (ref "U1") (pin "34") (pinfunction "PA13_34") (pintype "unspecified"))
    )
    (net (code "57") (name "PA15") (class "Default")
      (node (ref "H1") (pin "9") (pinfunction "9_9") (pintype "unspecified"))
      (node (ref "U1") (pin "38") (pinfunction "PA15_38") (pintype "unspecified"))
    )
    (net (code "58") (name "PB0") (class "Default")
      (node (ref "H2") (pin "5") (pinfunction "5_5") (pintype "unspecified"))
      (node (ref "R19") (pin "2") (pinfunction "2_2") (pintype "unspecified"))
      (node (ref "U1") (pin "18") (pinfunction "PB0_18") (pintype "unspecified"))
      (node (ref "U10") (pin "2") (pinfunction "A1_2") (pintype "unspecified"))
    )
    (net (code "59") (name "PB1") (class "Default")
      (node (ref "H2") (pin "4") (pinfunction "4_4") (pintype "unspecified"))
      (node (ref "R23") (pin "2") (pinfunction "2_2") (pintype "unspecified"))
      (node (ref "U1") (pin "19") (pinfunction "PB1_19") (pintype "unspecified"))
      (node (ref "U10") (pin "3") (pinfunction "A2_3") (pintype "unspecified"))
    )
    (net (code "60") (name "PB2") (class "Default")
      (node (ref "H2") (pin "3") (pinfunction "3_3") (pintype "unspecified"))
      (node (ref "R27") (pin "1") (pinfunction "1_1") (pintype "unspecified"))
      (node (ref "U1") (pin "20") (pinfunction "PB2_20") (pintype "unspecified"))
      (node (ref "U10") (pin "4") (pinfunction "A3_4") (pintype "unspecified"))
    )
    (net (code "61") (name "PB3") (class "Default")
      (node (ref "H1") (pin "8") (pinfunction "8_8") (pintype "unspecified"))
      (node (ref "R25") (pin "1") (pinfunction "1_1") (pintype "unspecified"))
      (node (ref "U1") (pin "39") (pinfunction "PB3_39") (pintype "unspecified"))
      (node (ref "U10") (pin "5") (pinfunction "A4_5") (pintype "unspecified"))
    )
    (net (code "62") (name "PB4") (class "Default")
      (node (ref "H1") (pin "7") (pinfunction "7_7") (pintype "unspecified"))
      (node (ref "R24") (pin "1") (pinfunction "1_1") (pintype "unspecified"))
      (node (ref "U1") (pin "40") (pinfunction "PB4_40") (pintype "unspecified"))
      (node (ref "U10") (pin "6") (pinfunction "A5_6") (pintype "unspecified"))
    )
    (net (code "63") (name "PB5") (class "Default")
      (node (ref "H1") (pin "6") (pinfunction "6_6") (pintype "unspecified"))
      (node (ref "R20") (pin "2") (pinfunction "2_2") (pintype "unspecified"))
      (node (ref "U1") (pin "41") (pinfunction "PB5_41") (pintype "unspecified"))
      (node (ref "U10") (pin "7") (pinfunction "A6_7") (pintype "unspecified"))
    )
    (net (code "64") (name "PB6") (class "Default")
      (node (ref "H1") (pin "5") (pinfunction "5_5") (pintype "unspecified"))
      (node (ref "R28") (pin "1") (pinfunction "1_1") (pintype "unspecified"))
      (node (ref "U1") (pin "42") (pinfunction "PB6_42") (pintype "unspecified"))
      (node (ref "U10") (pin "8") (pinfunction "A7_8") (pintype "unspecified"))
    )
    (net (code "65") (name "PB7") (class "Default")
      (node (ref "H1") (pin "4") (pinfunction "4_4") (pintype "unspecified"))
      (node (ref "R26") (pin "1") (pinfunction "1_1") (pintype "unspecified"))
      (node (ref "U1") (pin "43") (pinfunction "PB7_43") (pintype "unspecified"))
      (node (ref "U10") (pin "9") (pinfunction "A8_9") (pintype "unspecified"))
    )
    (net (code "66") (name "PB8") (class "Default")
      (node (ref "H1") (pin "3") (pinfunction "3_3") (pintype "unspecified"))
      (node (ref "U1") (pin "45") (pinfunction "PB8_45") (pintype "unspecified"))
    )
    (net (code "67") (name "PB9") (class "Default")
      (node (ref "H1") (pin "2") (pinfunction "2_2") (pintype "unspecified"))
      (node (ref "S1") (pin "2") (pinfunction "I/O_2") (pintype "unspecified"))
      (node (ref "U1") (pin "46") (pinfunction "PB9_46") (pintype "unspecified"))
    )
    (net (code "68") (name "PB10") (class "Default")
      (node (ref "R6") (pin "1") (pinfunction "1_1") (pintype "unspecified"))
      (node (ref "U1") (pin "21") (pinfunction "PB10_21") (pintype "unspecified"))
      (node (ref "U14") (pin "2") (pinfunction "2_2") (pintype "unspecified"))
    )
    (net (code "69") (name "PB11") (class "Default")
      (node (ref "R5") (pin "1") (pinfunction "1_1") (pintype "unspecified"))
      (node (ref "U1") (pin "22") (pinfunction "PB11_22") (pintype "unspecified"))
      (node (ref "U14") (pin "3") (pinfunction "3_3") (pintype "unspecified"))
    )
    (net (code "70") (name "PB12") (class "Default")
      (node (ref "H1") (pin "18") (pinfunction "18_18") (pintype "unspecified"))
      (node (ref "U1") (pin "25") (pinfunction "PB12_25") (pintype "unspecified"))
      (node (ref "U15") (pin "2") (pinfunction "2_2") (pintype "unspecified"))
    )
    (net (code "71") (name "PB13") (class "Default")
      (node (ref "H1") (pin "17") (pinfunction "17_17") (pintype "unspecified"))
      (node (ref "U1") (pin "26") (pinfunction "PB13_26") (pintype "unspecified"))
      (node (ref "U15") (pin "1") (pinfunction "1_1") (pintype "unspecified"))
    )
    (net (code "72") (name "PB14") (class "Default")
      (node (ref "H1") (pin "16") (pinfunction "16_16") (pintype "unspecified"))
      (node (ref "U1") (pin "27") (pinfunction "PB14_27") (pintype "unspecified"))
    )
    (net (code "73") (name "PB15") (class "Default")
      (node (ref "H1") (pin "15") (pinfunction "15_15") (pintype "unspecified"))
      (node (ref "U1") (pin "28") (pinfunction "PB15_28") (pintype "unspecified"))
      (node (ref "U15") (pin "3") (pinfunction "3_3") (pintype "unspecified"))
    )
    (net (code "74") (name "PC13") (class "Default")
      (node (ref "H2") (pin "16") (pinfunction "16_16") (pintype "unspecified"))
      (node (ref "U1") (pin "2") (pinfunction "PC13-TAMPER-RTC_2") (pintype "unspecified"))
    )
    (net (code "75") (name "PC14") (class "Default")
      (node (ref "H2") (pin "15") (pinfunction "15_15") (pintype "unspecified"))
      (node (ref "U1") (pin "3") (pinfunction "PC14-OSC32_IN_3") (pintype "unspecified"))
    )
    (net (code "76") (name "PC15") (class "Default")
      (node (ref "H2") (pin "14") (pinfunction "14_14") (pintype "unspecified"))
      (node (ref "U1") (pin "4") (pinfunction "PC15-OSC32_OUT_4") (pintype "unspecified"))
    )
    (net (code "77") (name "SWCLK") (class "Default")
      (node (ref "U1") (pin "37") (pinfunction "PA14_37") (pintype "unspecified"))
      (node (ref "U12") (pin "1") (pinfunction "1_1") (pintype "unspecified"))
    )
    (net (code "78") (name "SWIO") (class "Default")
      (node (ref "U1") (pin "33") (pinfunction "PA12_33") (pintype "unspecified"))
      (node (ref "U12") (pin "2") (pinfunction "2_2") (pintype "unspecified"))
    )
    (net (code "79") (name "unconnected-(S1-NC-Pad3)") (class "Default")
      (node (ref "S1") (pin "3") (pinfunction "NC_3") (pintype "unspecified+no_connect"))
    )
    (net (code "80") (name "unconnected-(U11-2Y0#-Pad12)") (class "Default")
      (node (ref "U11") (pin "12") (pinfunction "2Y0#_12") (pintype "unspecified+no_connect"))
    )
    (net (code "81") (name "unconnected-(U11-2Y2#-Pad10)") (class "Default")
      (node (ref "U11") (pin "10") (pinfunction "2Y2#_10") (pintype "unspecified+no_connect"))
    )
  )
)
